# 24-Power-P3V3_P1V8DPLL.net
KiCad netlist of a schematic drawn in Altium Designer
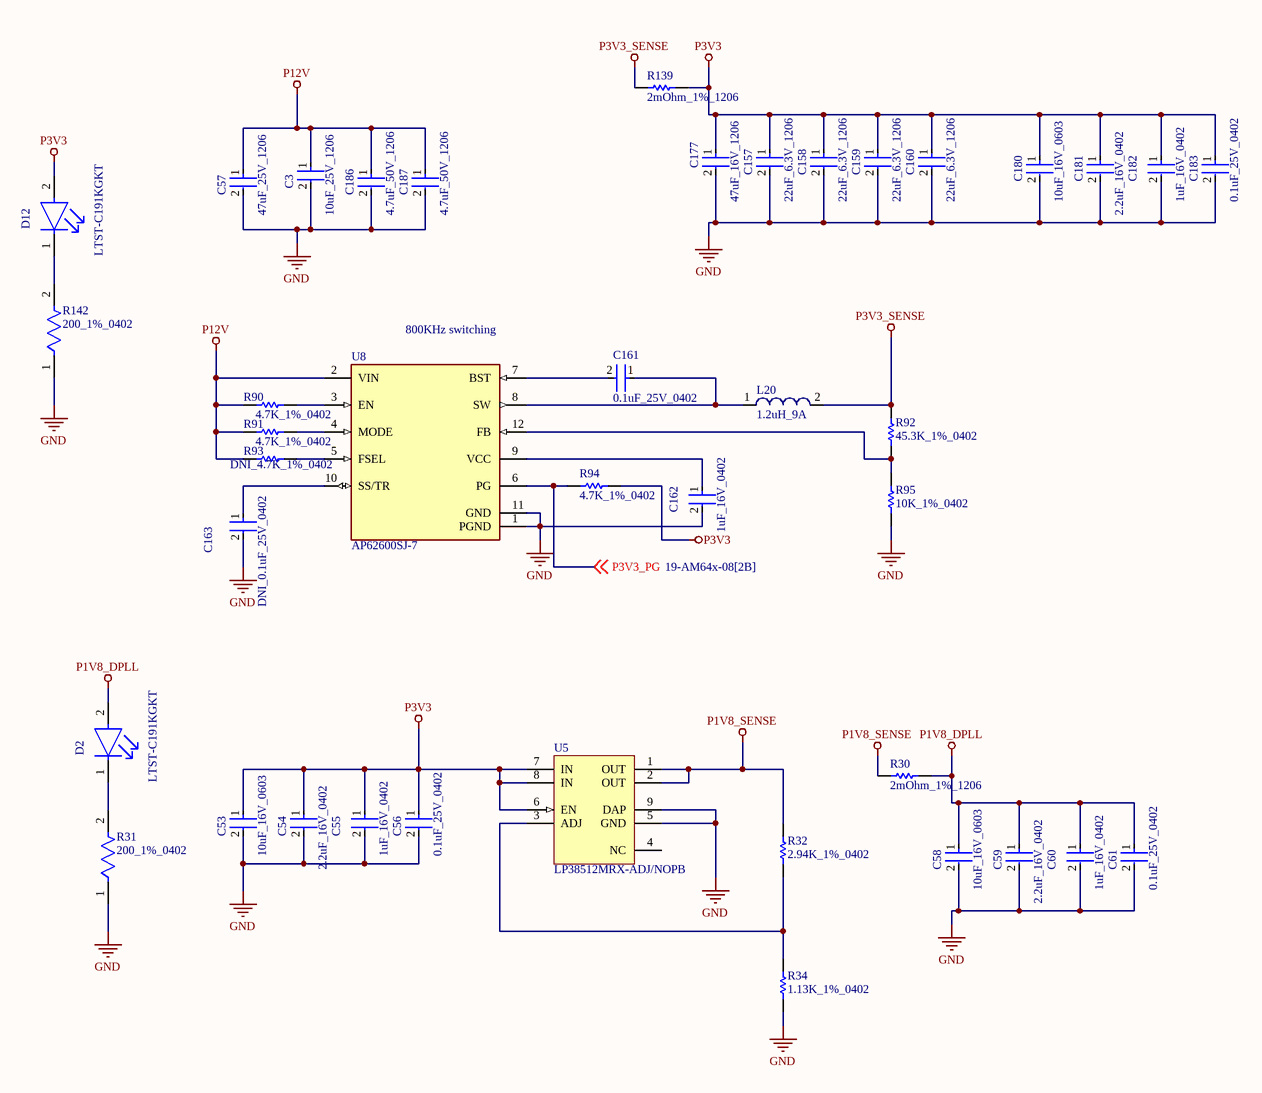
[diagram p0: 24-Power-P3V3_P1V8DPLL.SchDoc]

(export (version "E")
  (design (tool "Eeschema 10.0.6"))
  (components
    (comp (ref "C3")
      (value "10uF_25V_1206")
      (footprint "FP-1206-L_3_2_0_2-W_1_6_0-IPC_A")
      (description "General Purpose Ceramic Capacitor, 1206, 10uF, 20%, X5R, 15%, 25V")
      (fields (field (name "TOLERANCE") "20%"))
      (libsource (lib "Altium Content Vault") (part "02cd4be3c70576c341d710602a673aa"))
    )
    (comp (ref "C53")
      (value "10uF_16V_0603")
      (footprint "FP-0603-L_1_6_0_2-W_0_8_0-MFG")
      (description "Multilayer Ceramic Capacitor 10uF 16V X5R 20% SMD 0603 T/R")
      (fields (field (name "TOLERANCE") "20%"))
      (libsource (lib "Altium Content Vault") (part "b4654b650e69147ec39a6b967a45e02"))
    )
    (comp (ref "C54")
      (value "2.2uF_16V_0402")
      (footprint "FP-C1005-050-0_05-IPC_A")
      (description "Multilayer Ceramic Capacitors 2.2μF ±10% 16V X5R SMD 0402")
      (fields (field (name "TOLERANCE") "10%"))
      (libsource (lib "Altium Content Vault") (part "b4654b650e69147ec39a6b967a45e02"))
    )
    (comp (ref "C55")
      (value "1uF_16V_0402")
      (footprint "FP-0402-L_1_0_0_05-W_0_5-IPC_A")
      (description "None")
      (fields (field (name "TOLERANCE") "10%"))
      (libsource (lib "Altium Content Vault") (part "b4654b650e69147ec39a6b967a45e02"))
    )
    (comp (ref "C56")
      (value "0.1uF_25V_0402")
      (footprint "FP-0402-L_1_0_1-W_0_5_0_1-IPC_C")
      (description "General Purpose Ceramic Capacitor, 0402, 100nF, 10%, X7R, 15%, 25V")
      (fields (field (name "VOLTAGE") "25V") (field (name "TOLERANCE") "10%"))
      (libsource (lib "Altium Content Vault") (part "b4654b650e69147ec39a6b967a45e02"))
    )
    (comp (ref "C57")
      (value "47uF_25V_1206")
      (footprint "FP-C3216-160-0_2-MFG")
      (description "Multilayer Ceramic Capacitors 47uF ±20% 25V X5R SMD 1206")
      (fields (field (name "VOLTAGE") "25V") (field (name "TOLERANCE") "20%"))
      (libsource (lib "Altium Content Vault") (part "11868f565c42a9108669ba33697ecf6"))
    )
    (comp (ref "C58")
      (value "10uF_16V_0603")
      (footprint "FP-0603-L_1_6_0_2-W_0_8_0-MFG")
      (description "Multilayer Ceramic Capacitor 10uF 16V X5R 20% SMD 0603 T/R")
      (fields (field (name "TOLERANCE") "20%"))
      (libsource (lib "Altium Content Vault") (part "b4654b650e69147ec39a6b967a45e02"))
    )
    (comp (ref "C59")
      (value "2.2uF_16V_0402")
      (footprint "FP-C1005-050-0_05-IPC_A")
      (description "Multilayer Ceramic Capacitors 2.2μF ±10% 16V X5R SMD 0402")
      (fields (field (name "TOLERANCE") "10%"))
      (libsource (lib "Altium Content Vault") (part "b4654b650e69147ec39a6b967a45e02"))
    )
    (comp (ref "C60")
      (value "1uF_16V_0402")
      (footprint "FP-0402-L_1_0_0_05-W_0_5-IPC_A")
      (description "None")
      (fields (field (name "TOLERANCE") "10%"))
      (libsource (lib "Altium Content Vault") (part "b4654b650e69147ec39a6b967a45e02"))
    )
    (comp (ref "C61")
      (value "0.1uF_25V_0402")
      (footprint "FP-0402-L_1_0_1-W_0_5_0_1-IPC_C")
      (description "General Purpose Ceramic Capacitor, 0402, 100nF, 10%, X7R, 15%, 25V")
      (fields (field (name "VOLTAGE") "25V") (field (name "TOLERANCE") "10%"))
      (libsource (lib "Altium Content Vault") (part "b4654b650e69147ec39a6b967a45e02"))
    )
    (comp (ref "C157")
      (value "22uF_6.3V_1206")
      (footprint "FP-1206-L_3_2_0_2-W_1_6_0-IPC_C")
      (description "General Purpose Ceramic Capacitor, 1206, 22uF, 20%, X5R, 15%, 6.3V")
      (fields (field (name "TOLERANCE") "20%") (field (name "VOLTAGE") "6.3V"))
      (libsource (lib "Altium Content Vault") (part "02cd4be3c70576c341d710602a673aa"))
    )
    (comp (ref "C158")
      (value "22uF_6.3V_1206")
      (footprint "FP-1206-L_3_2_0_2-W_1_6_0-IPC_C")
      (description "General Purpose Ceramic Capacitor, 1206, 22uF, 20%, X5R, 15%, 6.3V")
      (fields (field (name "TOLERANCE") "20%") (field (name "VOLTAGE") "6.3V"))
      (libsource (lib "Altium Content Vault") (part "02cd4be3c70576c341d710602a673aa"))
    )
    (comp (ref "C159")
      (value "22uF_6.3V_1206")
      (footprint "FP-1206-L_3_2_0_2-W_1_6_0-IPC_C")
      (description "General Purpose Ceramic Capacitor, 1206, 22uF, 20%, X5R, 15%, 6.3V")
      (fields (field (name "TOLERANCE") "20%") (field (name "VOLTAGE") "6.3V"))
      (libsource (lib "Altium Content Vault") (part "02cd4be3c70576c341d710602a673aa"))
    )
    (comp (ref "C160")
      (value "22uF_6.3V_1206")
      (footprint "FP-1206-L_3_2_0_2-W_1_6_0-IPC_C")
      (description "General Purpose Ceramic Capacitor, 1206, 22uF, 20%, X5R, 15%, 6.3V")
      (fields (field (name "TOLERANCE") "20%") (field (name "VOLTAGE") "6.3V"))
      (libsource (lib "Altium Content Vault") (part "02cd4be3c70576c341d710602a673aa"))
    )
    (comp (ref "C161")
      (value "0.1uF_25V_0402")
      (footprint "FP-0402-L_1_0_1-W_0_5_0_1-IPC_C")
      (description "General Purpose Ceramic Capacitor, 0402, 100nF, 10%, X7R, 15%, 25V")
      (fields (field (name "VOLTAGE") "25V") (field (name "TOLERANCE") "10%"))
      (libsource (lib "Altium Content Vault") (part "b4654b650e69147ec39a6b967a45e02"))
    )
    (comp (ref "C162")
      (value "1uF_16V_0402")
      (footprint "FP-0402-L_1_0_0_05-W_0_5-IPC_A")
      (description "None")
      (fields (field (name "TOLERANCE") "10%"))
      (libsource (lib "Altium Content Vault") (part "b4654b650e69147ec39a6b967a45e02"))
    )
    (comp (ref "C163")
      (value "DNI_0.1uF_25V_0402")
      (footprint "FP-0402-L_1_0_1-W_0_5_0_1-IPC_C")
      (description "General Purpose Ceramic Capacitor, 0402, 100nF, 10%, X7R, 15%, 25V")
      (fields (field (name "VOLTAGE") "25V") (field (name "TOLERANCE") "10%"))
      (libsource (lib "Altium Content Vault") (part "b4654b650e69147ec39a6b967a45e02"))
    )
    (comp (ref "C177")
      (value "47uF_16V_1206")
      (footprint "FP-C3216-160-0_2-MFG")
      (description "Multilayer Ceramic Capacitors 47uF ±20% 16V X5R SMD 1206")
      (fields (field (name "TOLERANCE") "20%"))
      (libsource (lib "Altium Content Vault") (part "11868f565c42a9108669ba33697ecf6"))
    )
    (comp (ref "C180")
      (value "10uF_16V_0603")
      (footprint "FP-0603-L_1_6_0_2-W_0_8_0-MFG")
      (description "Multilayer Ceramic Capacitor 10uF 16V X5R 20% SMD 0603 T/R")
      (fields (field (name "TOLERANCE") "20%"))
      (libsource (lib "Altium Content Vault") (part "b4654b650e69147ec39a6b967a45e02"))
    )
    (comp (ref "C181")
      (value "2.2uF_16V_0402")
      (footprint "FP-C1005-050-0_05-IPC_A")
      (description "Multilayer Ceramic Capacitors 2.2μF ±10% 16V X5R SMD 0402")
      (fields (field (name "TOLERANCE") "10%"))
      (libsource (lib "Altium Content Vault") (part "b4654b650e69147ec39a6b967a45e02"))
    )
    (comp (ref "C182")
      (value "1uF_16V_0402")
      (footprint "FP-0402-L_1_0_0_05-W_0_5-IPC_A")
      (description "None")
      (fields (field (name "TOLERANCE") "10%"))
      (libsource (lib "Altium Content Vault") (part "b4654b650e69147ec39a6b967a45e02"))
    )
    (comp (ref "C183")
      (value "0.1uF_25V_0402")
      (footprint "FP-0402-L_1_0_1-W_0_5_0_1-IPC_C")
      (description "General Purpose Ceramic Capacitor, 0402, 100nF, 10%, X7R, 15%, 25V")
      (fields (field (name "VOLTAGE") "25V") (field (name "TOLERANCE") "10%"))
      (libsource (lib "Altium Content Vault") (part "b4654b650e69147ec39a6b967a45e02"))
    )
    (comp (ref "C186")
      (value "4.7uF_50V_1206")
      (footprint "FP-GRM31C-0_2-e0_3_0_8-IPC_C")
      (description "Chip Multilayer Ceramic Capacitors for General Purpose, 1206, 4.7uF, X7R, 15%, 10%, 50V")
      (fields (field (name "VOLTAGE") "50V") (field (name "TOLERANCE") "10%"))
      (libsource (lib "Altium Content Vault") (part "02cd4be3c70576c341d710602a673aa"))
    )
    (comp (ref "C187")
      (value "4.7uF_50V_1206")
      (footprint "FP-GRM31C-0_2-e0_3_0_8-IPC_C")
      (description "Chip Multilayer Ceramic Capacitors for General Purpose, 1206, 4.7uF, X7R, 15%, 10%, 50V")
      (fields (field (name "VOLTAGE") "50V") (field (name "TOLERANCE") "10%"))
      (libsource (lib "Altium Content Vault") (part "02cd4be3c70576c341d710602a673aa"))
    )
    (comp (ref "D2")
      (value "LTST-C191KGKT")
      (footprint "FP-LTST-C191KGKT-MFG")
      (description "LED GREEN CLEAR SMD")
      (libsource (lib "Altium Content Vault") (part "8706943c75ba83719d021d2fdc84c58"))
    )
    (comp (ref "D12")
      (value "LTST-C191KGKT")
      (footprint "FP-LTST-C191KGKT-MFG")
      (description "LED GREEN CLEAR SMD")
      (libsource (lib "Altium Content Vault") (part "8706943c75ba83719d021d2fdc84c58"))
    )
    (comp (ref "L20")
      (value "1.2uH_9A")
      (footprint "WE-LHMI 7050")
      (description "SMD Power Inductor WE-LHMI, L=1.2 µH")
      (fields (field (name "MANUFACTURER") "Wuerth Elektronik") (field (name "PARTNUMBER") "74437349012"))
      (libsource (lib "Altium Content Vault") (part "WE-IND-INDUCTOR-2"))
    )
    (comp (ref "R30")
      (value "2mOhm_1%_1206")
      (footprint "RESC3216X89X64NL25T25")
      (fields (field (name "MANUFACTURER") "Vishay Dale") (field (name "PART NUMBER") "WSL12062L000FEA18"))
      (libsource (lib "Altium Content Vault") (part "RES"))
    )
    (comp (ref "R31")
      (value "200_1%_0402")
      (footprint "FP-ERJ2RK-IPC_A")
      (description "RES SMD 200 OHM 1% 1/10W 0402")
      (fields (field (name "TOLERANCE") "1%"))
      (libsource (lib "Altium Content Vault") (part "1029c3af85768c4190bb7ad29bc67b5"))
    )
    (comp (ref "R32")
      (value "2.94K_1%_0402")
      (footprint "RESC1005X40X25ML05T10")
      (fields (field (name "MANUFACTURER") "Yageo") (field (name "PART NUMBER") "RC0402FR-072K94L"))
      (libsource (lib "Altium Content Vault") (part "RES"))
    )
    (comp (ref "R34")
      (value "1.13K_1%_0402")
      (footprint "RESC1005X40X25NL05T05")
      (fields (field (name "MANUFACTURER") "Panasonic") (field (name "PART NUMBER") "ERJ-2RKF1131X"))
      (libsource (lib "Altium Content Vault") (part "RES"))
    )
    (comp (ref "R90")
      (value "4.7K_1%_0402")
      (footprint "RESC1005X40X25NL10T10")
      (fields (field (name "MANUFACTURER") "Bourns") (field (name "PART NUMBER") "CR0402-FX-4701GLF"))
      (libsource (lib "Altium Content Vault") (part "RES"))
    )
    (comp (ref "R91")
      (value "4.7K_1%_0402")
      (footprint "RESC1005X40X25NL10T10")
      (fields (field (name "MANUFACTURER") "Bourns") (field (name "PART NUMBER") "CR0402-FX-4701GLF"))
      (libsource (lib "Altium Content Vault") (part "RES"))
    )
    (comp (ref "R92")
      (value "45.3K_1%_0402")
      (footprint "RESC1005X40X25ML05T10")
      (fields (field (name "PART NUMBER") "RC0402FR-0745K3L") (field (name "MANUFACTURER") "Yageo / Phycomp"))
      (libsource (lib "Altium Content Vault") (part "RES"))
    )
    (comp (ref "R93")
      (value "DNI_4.7K_1%_0402")
      (footprint "RESC1005X40X25NL10T10")
      (fields (field (name "MANUFACTURER") "Bourns") (field (name "PART NUMBER") "CR0402-FX-4701GLF"))
      (libsource (lib "Altium Content Vault") (part "RES"))
    )
    (comp (ref "R94")
      (value "4.7K_1%_0402")
      (footprint "RESC1005X40X25NL10T10")
      (fields (field (name "MANUFACTURER") "Bourns") (field (name "PART NUMBER") "CR0402-FX-4701GLF"))
      (libsource (lib "Altium Content Vault") (part "RES"))
    )
    (comp (ref "R95")
      (value "10K_1%_0402")
      (footprint "RESC1005X40X25NL10T10")
      (fields (field (name "MANUFACTURER") "Bourns") (field (name "PART NUMBER") "CR0402-FX-1002GLF"))
      (libsource (lib "Altium Content Vault") (part "RES"))
    )
    (comp (ref "R139")
      (value "2mOhm_1%_1206")
      (footprint "RESC3216X89X64NL25T25")
      (fields (field (name "MANUFACTURER") "Vishay Dale") (field (name "PART NUMBER") "WSL12062L000FEA18"))
      (libsource (lib "Altium Content Vault") (part "RES"))
    )
    (comp (ref "R142")
      (value "200_1%_0402")
      (footprint "FP-ERJ2RK-IPC_A")
      (description "RES SMD 200 OHM 1% 1/10W 0402")
      (fields (field (name "TOLERANCE") "1%"))
      (libsource (lib "Altium Content Vault") (part "1029c3af85768c4190bb7ad29bc67b5"))
    )
    (comp (ref "U5")
      (value "LP38512MRX-ADJ/NOPB")
      (footprint "MRA08B_M")
      (description "1.5A Fast-Transient Response Adjustable Low-Dropout Linear Voltage Regulator, 8-pin PSOP, Pb-Free")
      (fields (field (name "MANUFACTURER") "National Semiconductor"))
      (libsource (lib "Altium Content Vault") (part "PM-REG-LP38512MR-IL9"))
    )
    (comp (ref "U8")
      (value "AP62600SJ-7")
      (footprint "FP-V-QFN2030-12_Type_A-MFG")
      (description "DCDC CONV HV BUCK,V-QFN2030-12")
      (libsource (lib "Altium Content Vault") (part "03c86ce2703f4b33b3045e94f7be521"))
    )
  )
  (nets
    (net (code "1") (name "GND") (class "Default")
      (node (ref "C157") (pin "2") (pinfunction "2_2") (pintype "passive"))
      (node (ref "C158") (pin "2") (pinfunction "2_2") (pintype "passive"))
      (node (ref "C159") (pin "2") (pinfunction "2_2") (pintype "passive"))
      (node (ref "C160") (pin "2") (pinfunction "2_2") (pintype "passive"))
      (node (ref "C162") (pin "2") (pinfunction "2_2") (pintype "passive"))
      (node (ref "C163") (pin "2") (pinfunction "2_2") (pintype "passive"))
      (node (ref "C177") (pin "2") (pinfunction "2_2") (pintype "passive"))
      (node (ref "C180") (pin "2") (pinfunction "2_2") (pintype "passive"))
      (node (ref "C181") (pin "2") (pinfunction "2_2") (pintype "passive"))
      (node (ref "C182") (pin "2") (pinfunction "2_2") (pintype "passive"))
      (node (ref "C183") (pin "2") (pinfunction "2_2") (pintype "passive"))
      (node (ref "C186") (pin "2") (pinfunction "2_2") (pintype "passive"))
      (node (ref "C187") (pin "2") (pinfunction "2_2") (pintype "passive"))
      (node (ref "C3") (pin "2") (pinfunction "2_2") (pintype "passive"))
      (node (ref "C53") (pin "2") (pinfunction "2_2") (pintype "passive"))
      (node (ref "C54") (pin "2") (pinfunction "2_2") (pintype "passive"))
      (node (ref "C55") (pin "2") (pinfunction "2_2") (pintype "passive"))
      (node (ref "C56") (pin "2") (pinfunction "2_2") (pintype "passive"))
      (node (ref "C57") (pin "2") (pinfunction "2_2") (pintype "passive"))
      (node (ref "C58") (pin "2") (pinfunction "2_2") (pintype "passive"))
      (node (ref "C59") (pin "2") (pinfunction "2_2") (pintype "passive"))
      (node (ref "C60") (pin "2") (pinfunction "2_2") (pintype "passive"))
      (node (ref "C61") (pin "2") (pinfunction "2_2") (pintype "passive"))
      (node (ref "R142") (pin "1") (pinfunction "1_1") (pintype "passive"))
      (node (ref "R31") (pin "1") (pinfunction "1_1") (pintype "passive"))
      (node (ref "R34") (pin "1") (pinfunction "1_1") (pintype "passive"))
      (node (ref "R95") (pin "1") (pinfunction "1_1") (pintype "passive"))
      (node (ref "U5") (pin "5") (pinfunction "GND_5") (pintype "power_in"))
      (node (ref "U5") (pin "9") (pinfunction "DAP_9") (pintype "passive"))
      (node (ref "U8") (pin "1") (pinfunction "PGND_1") (pintype "power_in"))
      (node (ref "U8") (pin "11") (pinfunction "GND_11") (pintype "power_in"))
    )
    (net (code "2") (name "Net-(D2-C)") (class "Default")
      (node (ref "D2") (pin "1") (pinfunction "C_1") (pintype "passive"))
      (node (ref "R31") (pin "2") (pinfunction "2_2") (pintype "passive"))
    )
    (net (code "3") (name "Net-(D12-C)") (class "Default")
      (node (ref "D12") (pin "1") (pinfunction "C_1") (pintype "passive"))
      (node (ref "R142") (pin "2") (pinfunction "2_2") (pintype "passive"))
    )
    (net (code "4") (name "Net-(U5-ADJ)") (class "Default")
      (node (ref "R32") (pin "1") (pinfunction "1_1") (pintype "passive"))
      (node (ref "R34") (pin "2") (pinfunction "2_2") (pintype "passive"))
      (node (ref "U5") (pin "3") (pinfunction "ADJ_3") (pintype "passive"))
    )
    (net (code "5") (name "Net-(U8-BST)") (class "Default")
      (node (ref "C161") (pin "2") (pinfunction "2_2") (pintype "passive"))
      (node (ref "U8") (pin "7") (pinfunction "BST_7") (pintype "input"))
    )
    (net (code "6") (name "Net-(U8-EN)") (class "Default")
      (node (ref "R90") (pin "2") (pinfunction "2_2") (pintype "passive"))
      (node (ref "U8") (pin "3") (pinfunction "EN_3") (pintype "input"))
    )
    (net (code "7") (name "Net-(U8-FB)") (class "Default")
      (node (ref "R92") (pin "1") (pinfunction "1_1") (pintype "passive"))
      (node (ref "R95") (pin "2") (pinfunction "2_2") (pintype "passive"))
      (node (ref "U8") (pin "12") (pinfunction "FB_12") (pintype "input"))
    )
    (net (code "8") (name "Net-(U8-FSEL)") (class "Default")
      (node (ref "R93") (pin "2") (pinfunction "2_2") (pintype "passive"))
      (node (ref "U8") (pin "5") (pinfunction "FSEL_5") (pintype "input"))
    )
    (net (code "9") (name "Net-(U8-MODE)") (class "Default")
      (node (ref "R91") (pin "2") (pinfunction "2_2") (pintype "passive"))
      (node (ref "U8") (pin "4") (pinfunction "MODE_4") (pintype "input"))
    )
    (net (code "10") (name "Net-(U8-SS{slash}TR)") (class "Default")
      (node (ref "C163") (pin "1") (pinfunction "1_1") (pintype "passive"))
      (node (ref "U8") (pin "10") (pinfunction "SS/TR_10") (pintype "bidirectional"))
    )
    (net (code "11") (name "Net-(U8-SW)") (class "Default")
      (node (ref "C161") (pin "1") (pinfunction "1_1") (pintype "passive"))
      (node (ref "L20") (pin "1") (pinfunction "1_1") (pintype "passive"))
      (node (ref "U8") (pin "8") (pinfunction "SW_8") (pintype "output"))
    )
    (net (code "12") (name "Net-(U8-VCC)") (class "Default")
      (node (ref "C162") (pin "1") (pinfunction "1_1") (pintype "passive"))
      (node (ref "U8") (pin "9") (pinfunction "VCC_9") (pintype "power_in"))
    )
    (net (code "13") (name "P1V8_DPLL") (class "Default")
      (node (ref "C58") (pin "1") (pinfunction "1_1") (pintype "passive"))
      (node (ref "C59") (pin "1") (pinfunction "1_1") (pintype "passive"))
      (node (ref "C60") (pin "1") (pinfunction "1_1") (pintype "passive"))
      (node (ref "C61") (pin "1") (pinfunction "1_1") (pintype "passive"))
      (node (ref "D2") (pin "2") (pinfunction "A_2") (pintype "passive"))
      (node (ref "R30") (pin "2") (pinfunction "2_2") (pintype "passive"))
    )
    (net (code "14") (name "P1V8_SENSE") (class "Default")
      (node (ref "R30") (pin "1") (pinfunction "1_1") (pintype "passive"))
      (node (ref "R32") (pin "2") (pinfunction "2_2") (pintype "passive"))
      (node (ref "U5") (pin "1") (pinfunction "OUT_1") (pintype "power_in"))
      (node (ref "U5") (pin "2") (pinfunction "OUT_2") (pintype "power_in"))
    )
    (net (code "15") (name "P3V3") (class "Default")
      (node (ref "C157") (pin "1") (pinfunction "1_1") (pintype "passive"))
      (node (ref "C158") (pin "1") (pinfunction "1_1") (pintype "passive"))
      (node (ref "C159") (pin "1") (pinfunction "1_1") (pintype "passive"))
      (node (ref "C160") (pin "1") (pinfunction "1_1") (pintype "passive"))
      (node (ref "C177") (pin "1") (pinfunction "1_1") (pintype "passive"))
      (node (ref "C180") (pin "1") (pinfunction "1_1") (pintype "passive"))
      (node (ref "C181") (pin "1") (pinfunction "1_1") (pintype "passive"))
      (node (ref "C182") (pin "1") (pinfunction "1_1") (pintype "passive"))
      (node (ref "C183") (pin "1") (pinfunction "1_1") (pintype "passive"))
      (node (ref "C53") (pin "1") (pinfunction "1_1") (pintype "passive"))
      (node (ref "C54") (pin "1") (pinfunction "1_1") (pintype "passive"))
      (node (ref "C55") (pin "1") (pinfunction "1_1") (pintype "passive"))
      (node (ref "C56") (pin "1") (pinfunction "1_1") (pintype "passive"))
      (node (ref "D12") (pin "2") (pinfunction "A_2") (pintype "passive"))
      (node (ref "R139") (pin "2") (pinfunction "2_2") (pintype "passive"))
      (node (ref "R94") (pin "1") (pinfunction "1_1") (pintype "passive"))
      (node (ref "U5") (pin "6") (pinfunction "EN_6") (pintype "input"))
      (node (ref "U5") (pin "7") (pinfunction "IN_7") (pintype "power_in"))
      (node (ref "U5") (pin "8") (pinfunction "IN_8") (pintype "power_in"))
    )
    (net (code "16") (name "P3V3_PG") (class "Default")
      (node (ref "R94") (pin "2") (pinfunction "2_2") (pintype "passive"))
      (node (ref "U8") (pin "6") (pinfunction "PG_6") (pintype "open_collector"))
    )
    (net (code "17") (name "P3V3_SENSE") (class "Default")
      (node (ref "L20") (pin "2") (pinfunction "2_2") (pintype "passive"))
      (node (ref "R139") (pin "1") (pinfunction "1_1") (pintype "passive"))
      (node (ref "R92") (pin "2") (pinfunction "2_2") (pintype "passive"))
    )
    (net (code "18") (name "P12V") (class "Default")
      (node (ref "C186") (pin "1") (pinfunction "1_1") (pintype "passive"))
      (node (ref "C187") (pin "1") (pinfunction "1_1") (pintype "passive"))
      (node (ref "C3") (pin "1") (pinfunction "1_1") (pintype "passive"))
      (node (ref "C57") (pin "1") (pinfunction "1_1") (pintype "passive"))
      (node (ref "R90") (pin "1") (pinfunction "1_1") (pintype "passive"))
      (node (ref "R91") (pin "1") (pinfunction "1_1") (pintype "passive"))
      (node (ref "R93") (pin "1") (pinfunction "1_1") (pintype "passive"))
      (node (ref "U8") (pin "2") (pinfunction "VIN_2") (pintype "power_in"))
    )
    (net (code "19") (name "unconnected-(U5-NC-Pad4)") (class "Default")
      (node (ref "U5") (pin "4") (pinfunction "NC_4") (pintype "passive"))
    )
  )
)
